# OBKP_Effector_PCB_MIKE_DID_IT.net
KiCad netlist of a schematic drawn in EAGLE
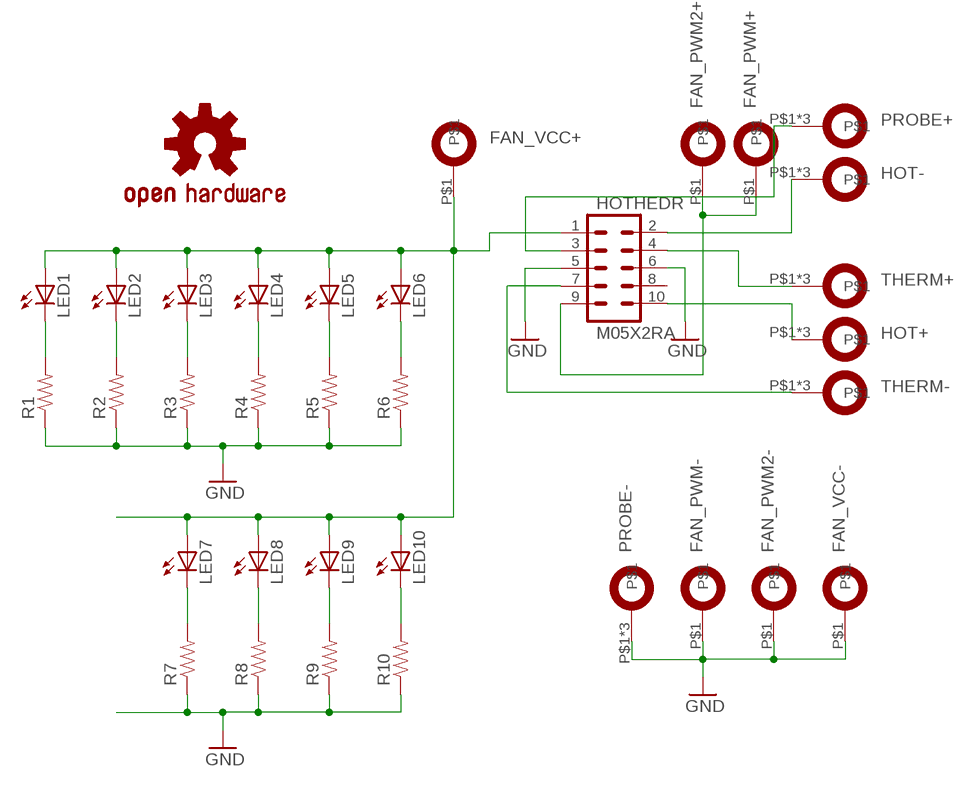
[diagram p0: schematic, sheet 1]

(export (version "E")
  (design (tool "Eeschema 10.0.6"))
  (components
    (comp (ref "FAN_PWM+")
      (value "LUG2.3")
      (footprint "eagle-import:2.3MM")
      (libsource (lib "eagle-import") (part "LUG2.3"))
    )
    (comp (ref "FAN_PWM-")
      (value "LUG2.3")
      (footprint "eagle-import:2.3MM")
      (libsource (lib "eagle-import") (part "LUG2.3"))
    )
    (comp (ref "FAN_PWM2+")
      (value "LUG2.3")
      (footprint "eagle-import:2.3MM")
      (libsource (lib "eagle-import") (part "LUG2.3"))
    )
    (comp (ref "FAN_PWM2-")
      (value "LUG2.3")
      (footprint "eagle-import:2.3MM")
      (libsource (lib "eagle-import") (part "LUG2.3"))
    )
    (comp (ref "FAN_VCC+")
      (value "LUG2.3")
      (footprint "eagle-import:2.3MM")
      (libsource (lib "eagle-import") (part "LUG2.3"))
    )
    (comp (ref "FAN_VCC-")
      (value "LUG2.3")
      (footprint "eagle-import:2.3MM")
      (libsource (lib "eagle-import") (part "LUG2.3"))
    )
    (comp (ref "HOT+")
      (value "LUG3-X")
      (footprint "eagle-import:3MM")
      (libsource (lib "eagle-import") (part "LUG3-X"))
    )
    (comp (ref "HOT-")
      (value "LUG3-X")
      (footprint "eagle-import:3MM")
      (libsource (lib "eagle-import") (part "LUG3-X"))
    )
    (comp (ref "HOTHEDR")
      (value "M05X2RA")
      (footprint "eagle-import:2X5-RA")
      (libsource (lib "eagle-import") (part "M05X2RA"))
    )
    (comp (ref "LED1")
      (value "LED0805")
      (footprint "eagle-import:CHIPLED_0805")
      (libsource (lib "eagle-import") (part "LED0805"))
    )
    (comp (ref "LED2")
      (value "LED0805")
      (footprint "eagle-import:CHIPLED_0805")
      (libsource (lib "eagle-import") (part "LED0805"))
    )
    (comp (ref "LED3")
      (value "LED0805")
      (footprint "eagle-import:CHIPLED_0805")
      (libsource (lib "eagle-import") (part "LED0805"))
    )
    (comp (ref "LED4")
      (value "LED0805")
      (footprint "eagle-import:CHIPLED_0805")
      (libsource (lib "eagle-import") (part "LED0805"))
    )
    (comp (ref "LED5")
      (value "LED0805")
      (footprint "eagle-import:CHIPLED_0805")
      (libsource (lib "eagle-import") (part "LED0805"))
    )
    (comp (ref "LED6")
      (value "LED0805")
      (footprint "eagle-import:CHIPLED_0805")
      (libsource (lib "eagle-import") (part "LED0805"))
    )
    (comp (ref "LED7")
      (value "LED0805")
      (footprint "eagle-import:CHIPLED_0805")
      (libsource (lib "eagle-import") (part "LED0805"))
    )
    (comp (ref "LED8")
      (value "LED0805")
      (footprint "eagle-import:CHIPLED_0805")
      (libsource (lib "eagle-import") (part "LED0805"))
    )
    (comp (ref "LED9")
      (value "LED0805")
      (footprint "eagle-import:CHIPLED_0805")
      (libsource (lib "eagle-import") (part "LED0805"))
    )
    (comp (ref "LED10")
      (value "LED0805")
      (footprint "eagle-import:CHIPLED_0805")
      (libsource (lib "eagle-import") (part "LED0805"))
    )
    (comp (ref "LOGO1")
      (value "OSHW-LOGOS")
      (footprint "eagle-import:OSHW-LOGO-S")
      (libsource (lib "eagle-import") (part "OSHW-LOGOS"))
    )
    (comp (ref "PROBE+")
      (value "LUG3-X")
      (footprint "eagle-import:3MM")
      (libsource (lib "eagle-import") (part "LUG3-X"))
    )
    (comp (ref "PROBE-")
      (value "LUG3-X")
      (footprint "eagle-import:3MM")
      (libsource (lib "eagle-import") (part "LUG3-X"))
    )
    (comp (ref "R1")
      (value "RESISTOR0805-RES")
      (footprint "eagle-import:0805")
      (libsource (lib "eagle-import") (part "RESISTOR0805-RES"))
    )
    (comp (ref "R2")
      (value "RESISTOR0805-RES")
      (footprint "eagle-import:0805")
      (libsource (lib "eagle-import") (part "RESISTOR0805-RES"))
    )
    (comp (ref "R3")
      (value "RESISTOR0805-RES")
      (footprint "eagle-import:0805")
      (libsource (lib "eagle-import") (part "RESISTOR0805-RES"))
    )
    (comp (ref "R4")
      (value "RESISTOR0805-RES")
      (footprint "eagle-import:0805")
      (libsource (lib "eagle-import") (part "RESISTOR0805-RES"))
    )
    (comp (ref "R5")
      (value "RESISTOR0805-RES")
      (footprint "eagle-import:0805")
      (libsource (lib "eagle-import") (part "RESISTOR0805-RES"))
    )
    (comp (ref "R6")
      (value "RESISTOR0805-RES")
      (footprint "eagle-import:0805")
      (libsource (lib "eagle-import") (part "RESISTOR0805-RES"))
    )
    (comp (ref "R7")
      (value "RESISTOR0805-RES")
      (footprint "eagle-import:0805")
      (libsource (lib "eagle-import") (part "RESISTOR0805-RES"))
    )
    (comp (ref "R8")
      (value "RESISTOR0805-RES")
      (footprint "eagle-import:0805")
      (libsource (lib "eagle-import") (part "RESISTOR0805-RES"))
    )
    (comp (ref "R9")
      (value "RESISTOR0805-RES")
      (footprint "eagle-import:0805")
      (libsource (lib "eagle-import") (part "RESISTOR0805-RES"))
    )
    (comp (ref "R10")
      (value "RESISTOR0805-RES")
      (footprint "eagle-import:0805")
      (libsource (lib "eagle-import") (part "RESISTOR0805-RES"))
    )
    (comp (ref "THERM+")
      (value "LUG3-X")
      (footprint "eagle-import:3MM")
      (libsource (lib "eagle-import") (part "LUG3-X"))
    )
    (comp (ref "THERM-")
      (value "LUG3-X")
      (footprint "eagle-import:3MM")
      (libsource (lib "eagle-import") (part "LUG3-X"))
    )
  )
  (nets
    (net (code "1") (name "GND") (class "Default")
      (node (ref "FAN_PWM-") (pin "P$1") (pinfunction "P$1_P$1") (pintype "bidirectional"))
      (node (ref "FAN_PWM2-") (pin "P$1") (pinfunction "P$1_P$1") (pintype "bidirectional"))
      (node (ref "FAN_VCC-") (pin "P$1") (pinfunction "P$1_P$1") (pintype "bidirectional"))
      (node (ref "HOTHEDR") (pin "5") (pinfunction "5_5") (pintype "passive"))
      (node (ref "HOTHEDR") (pin "6") (pinfunction "6_6") (pintype "passive"))
      (node (ref "PROBE-") (pin "P$1") (pinfunction "P$1_P$1") (pintype "bidirectional"))
      (node (ref "PROBE-") (pin "P$2") (pinfunction "P$1_P$2") (pintype "bidirectional"))
      (node (ref "PROBE-") (pin "P$3") (pinfunction "P$1_P$3") (pintype "bidirectional"))
      (node (ref "R1") (pin "1") (pinfunction "1_1") (pintype "passive"))
      (node (ref "R10") (pin "1") (pinfunction "1_1") (pintype "passive"))
      (node (ref "R2") (pin "1") (pinfunction "1_1") (pintype "passive"))
      (node (ref "R3") (pin "1") (pinfunction "1_1") (pintype "passive"))
      (node (ref "R4") (pin "1") (pinfunction "1_1") (pintype "passive"))
      (node (ref "R5") (pin "1") (pinfunction "1_1") (pintype "passive"))
      (node (ref "R6") (pin "1") (pinfunction "1_1") (pintype "passive"))
      (node (ref "R7") (pin "1") (pinfunction "1_1") (pintype "passive"))
      (node (ref "R8") (pin "1") (pinfunction "1_1") (pintype "passive"))
      (node (ref "R9") (pin "1") (pinfunction "1_1") (pintype "passive"))
    )
    (net (code "2") (name "Net-(FAN_PWM+-PadP$1)") (class "Default")
      (node (ref "FAN_PWM+") (pin "P$1") (pinfunction "P$1_P$1") (pintype "bidirectional"))
      (node (ref "FAN_PWM2+") (pin "P$1") (pinfunction "P$1_P$1") (pintype "bidirectional"))
      (node (ref "HOTHEDR") (pin "9") (pinfunction "9_9") (pintype "passive"))
    )
    (net (code "3") (name "Net-(FAN_VCC+-PadP$1)") (class "Default")
      (node (ref "FAN_VCC+") (pin "P$1") (pinfunction "P$1_P$1") (pintype "bidirectional"))
      (node (ref "HOTHEDR") (pin "1") (pinfunction "1_1") (pintype "passive"))
      (node (ref "LED1") (pin "A") (pinfunction "A_A") (pintype "passive"))
      (node (ref "LED10") (pin "A") (pinfunction "A_A") (pintype "passive"))
      (node (ref "LED2") (pin "A") (pinfunction "A_A") (pintype "passive"))
      (node (ref "LED3") (pin "A") (pinfunction "A_A") (pintype "passive"))
      (node (ref "LED4") (pin "A") (pinfunction "A_A") (pintype "passive"))
      (node (ref "LED5") (pin "A") (pinfunction "A_A") (pintype "passive"))
      (node (ref "LED6") (pin "A") (pinfunction "A_A") (pintype "passive"))
      (node (ref "LED7") (pin "A") (pinfunction "A_A") (pintype "passive"))
      (node (ref "LED8") (pin "A") (pinfunction "A_A") (pintype "passive"))
      (node (ref "LED9") (pin "A") (pinfunction "A_A") (pintype "passive"))
    )
    (net (code "4") (name "Net-(HOT+-P$1-PadP$2)") (class "Default")
      (node (ref "HOT+") (pin "P$1") (pinfunction "P$1_P$1") (pintype "bidirectional"))
      (node (ref "HOT+") (pin "P$2") (pinfunction "P$1_P$2") (pintype "bidirectional"))
      (node (ref "HOT+") (pin "P$3") (pinfunction "P$1_P$3") (pintype "bidirectional"))
      (node (ref "HOTHEDR") (pin "10") (pinfunction "10_10") (pintype "passive"))
    )
    (net (code "5") (name "Net-(HOT--P$1-PadP$2)") (class "Default")
      (node (ref "HOT-") (pin "P$1") (pinfunction "P$1_P$1") (pintype "bidirectional"))
      (node (ref "HOT-") (pin "P$2") (pinfunction "P$1_P$2") (pintype "bidirectional"))
      (node (ref "HOT-") (pin "P$3") (pinfunction "P$1_P$3") (pintype "bidirectional"))
      (node (ref "HOTHEDR") (pin "2") (pinfunction "2_2") (pintype "passive"))
    )
    (net (code "6") (name "Net-(HOTHEDR-Pad3)") (class "Default")
      (node (ref "HOTHEDR") (pin "3") (pinfunction "3_3") (pintype "passive"))
      (node (ref "PROBE+") (pin "P$1") (pinfunction "P$1_P$1") (pintype "bidirectional"))
      (node (ref "PROBE+") (pin "P$2") (pinfunction "P$1_P$2") (pintype "bidirectional"))
      (node (ref "PROBE+") (pin "P$3") (pinfunction "P$1_P$3") (pintype "bidirectional"))
    )
    (net (code "7") (name "Net-(HOTHEDR-Pad4)") (class "Default")
      (node (ref "HOTHEDR") (pin "4") (pinfunction "4_4") (pintype "passive"))
      (node (ref "THERM+") (pin "P$1") (pinfunction "P$1_P$1") (pintype "bidirectional"))
      (node (ref "THERM+") (pin "P$2") (pinfunction "P$1_P$2") (pintype "bidirectional"))
      (node (ref "THERM+") (pin "P$3") (pinfunction "P$1_P$3") (pintype "bidirectional"))
    )
    (net (code "8") (name "Net-(HOTHEDR-Pad7)") (class "Default")
      (node (ref "HOTHEDR") (pin "7") (pinfunction "7_7") (pintype "passive"))
      (node (ref "THERM-") (pin "P$1") (pinfunction "P$1_P$1") (pintype "bidirectional"))
      (node (ref "THERM-") (pin "P$2") (pinfunction "P$1_P$2") (pintype "bidirectional"))
      (node (ref "THERM-") (pin "P$3") (pinfunction "P$1_P$3") (pintype "bidirectional"))
    )
    (net (code "9") (name "Net-(LED1-PadC)") (class "Default")
      (node (ref "LED1") (pin "C") (pinfunction "C_C") (pintype "passive"))
      (node (ref "R1") (pin "2") (pinfunction "2_2") (pintype "passive"))
    )
    (net (code "10") (name "Net-(LED2-PadC)") (class "Default")
      (node (ref "LED2") (pin "C") (pinfunction "C_C") (pintype "passive"))
      (node (ref "R2") (pin "2") (pinfunction "2_2") (pintype "passive"))
    )
    (net (code "11") (name "Net-(LED3-PadC)") (class "Default")
      (node (ref "LED3") (pin "C") (pinfunction "C_C") (pintype "passive"))
      (node (ref "R3") (pin "2") (pinfunction "2_2") (pintype "passive"))
    )
    (net (code "12") (name "Net-(LED4-PadC)") (class "Default")
      (node (ref "LED4") (pin "C") (pinfunction "C_C") (pintype "passive"))
      (node (ref "R4") (pin "2") (pinfunction "2_2") (pintype "passive"))
    )
    (net (code "13") (name "Net-(LED5-PadC)") (class "Default")
      (node (ref "LED5") (pin "C") (pinfunction "C_C") (pintype "passive"))
      (node (ref "R5") (pin "2") (pinfunction "2_2") (pintype "passive"))
    )
    (net (code "14") (name "Net-(LED6-PadC)") (class "Default")
      (node (ref "LED6") (pin "C") (pinfunction "C_C") (pintype "passive"))
      (node (ref "R6") (pin "2") (pinfunction "2_2") (pintype "passive"))
    )
    (net (code "15") (name "Net-(LED7-PadC)") (class "Default")
      (node (ref "LED7") (pin "C") (pinfunction "C_C") (pintype "passive"))
      (node (ref "R7") (pin "2") (pinfunction "2_2") (pintype "passive"))
    )
    (net (code "16") (name "Net-(LED8-PadC)") (class "Default")
      (node (ref "LED8") (pin "C") (pinfunction "C_C") (pintype "passive"))
      (node (ref "R8") (pin "2") (pinfunction "2_2") (pintype "passive"))
    )
    (net (code "17") (name "Net-(LED9-PadC)") (class "Default")
      (node (ref "LED9") (pin "C") (pinfunction "C_C") (pintype "passive"))
      (node (ref "R9") (pin "2") (pinfunction "2_2") (pintype "passive"))
    )
    (net (code "18") (name "Net-(LED10-PadC)") (class "Default")
      (node (ref "LED10") (pin "C") (pinfunction "C_C") (pintype "passive"))
      (node (ref "R10") (pin "2") (pinfunction "2_2") (pintype "passive"))
    )
    (net (code "19") (name "unconnected-(HOTHEDR-Pad8)") (class "Default")
      (node (ref "HOTHEDR") (pin "8") (pinfunction "8_8") (pintype "passive"))
    )
  )
)
